# Interface1.net
KiCad netlist of a schematic drawn in Altium Designer
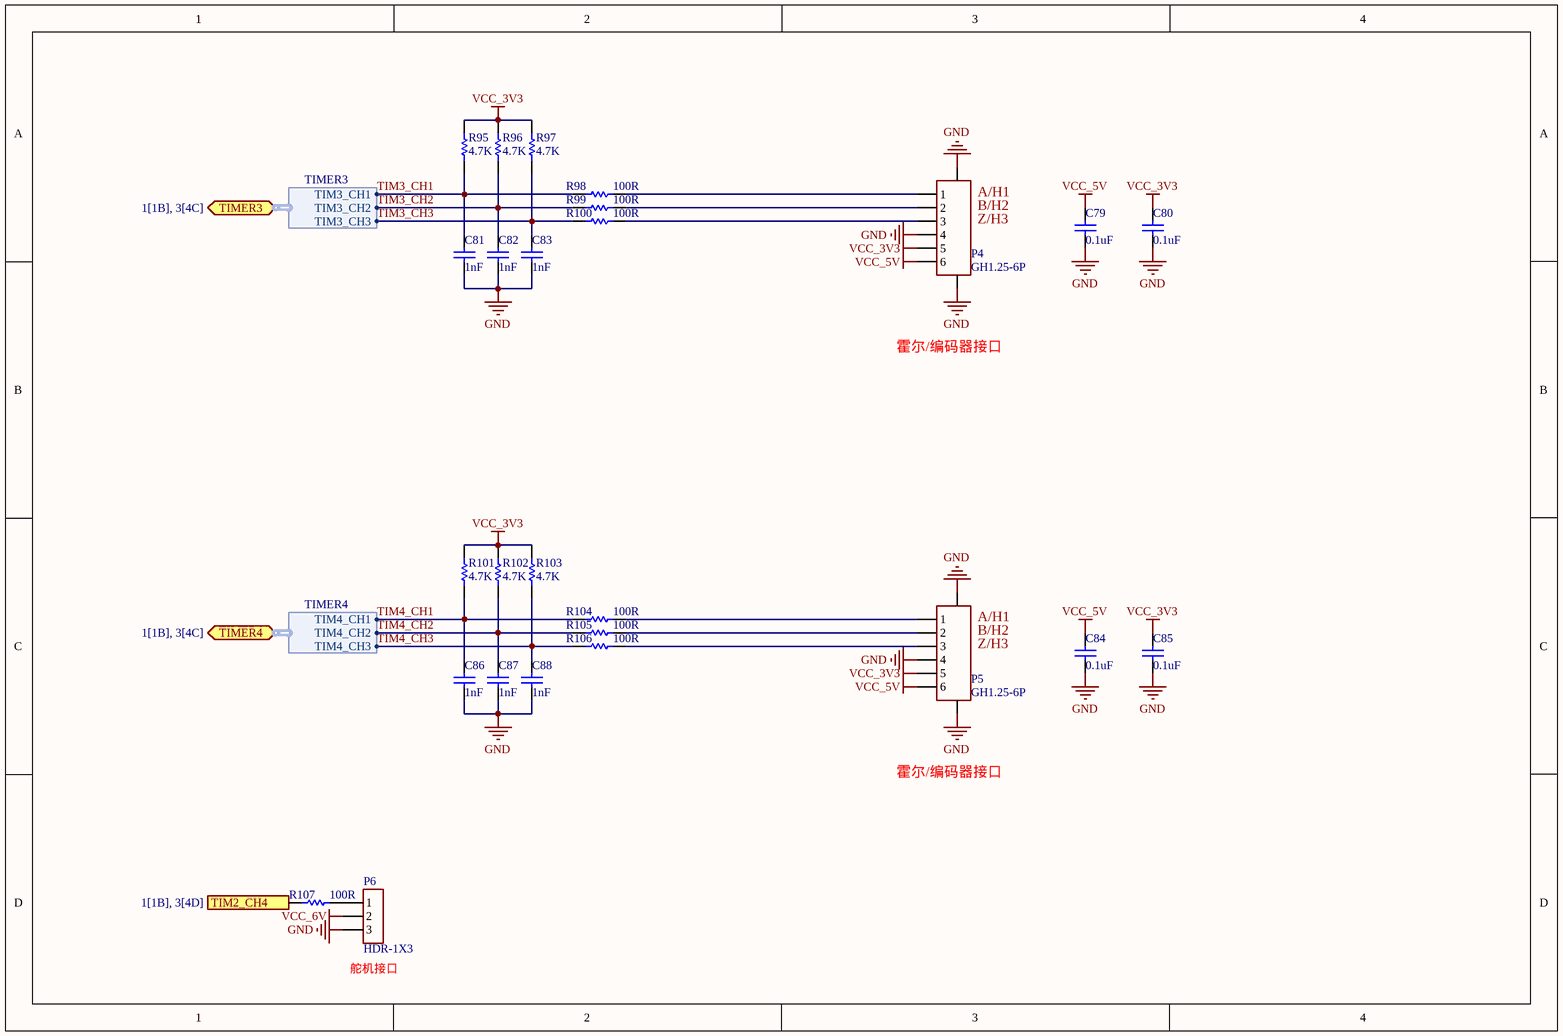
[diagram p0: Interface1.SchDoc]

(export (version "E")
  (design (tool "Eeschema 10.0.6"))
  (components
    (comp (ref "C79")
      (value "0.1uF")
      (footprint "C0603_NS")
      (description "Capacitor")
      (libsource (lib "Miscellaneous Devices") (part "Cap"))
    )
    (comp (ref "C80")
      (value "0.1uF")
      (footprint "C0603_NS")
      (description "Capacitor")
      (libsource (lib "Miscellaneous Devices") (part "Cap"))
    )
    (comp (ref "C81")
      (value "1nF")
      (footprint "C0603_NS")
      (description "Capacitor")
      (libsource (lib "Miscellaneous Devices") (part "Cap"))
    )
    (comp (ref "C82")
      (value "1nF")
      (footprint "C0603_NS")
      (description "Capacitor")
      (libsource (lib "Miscellaneous Devices") (part "Cap"))
    )
    (comp (ref "C83")
      (value "1nF")
      (footprint "C0603_NS")
      (description "Capacitor")
      (libsource (lib "Miscellaneous Devices") (part "Cap"))
    )
    (comp (ref "C84")
      (value "0.1uF")
      (footprint "C0603_NS")
      (description "Capacitor")
      (libsource (lib "Miscellaneous Devices") (part "Cap"))
    )
    (comp (ref "C85")
      (value "0.1uF")
      (footprint "C0603_NS")
      (description "Capacitor")
      (libsource (lib "Miscellaneous Devices") (part "Cap"))
    )
    (comp (ref "C86")
      (value "1nF")
      (footprint "C0603_NS")
      (description "Capacitor")
      (libsource (lib "Miscellaneous Devices") (part "Cap"))
    )
    (comp (ref "C87")
      (value "1nF")
      (footprint "C0603_NS")
      (description "Capacitor")
      (libsource (lib "Miscellaneous Devices") (part "Cap"))
    )
    (comp (ref "C88")
      (value "1nF")
      (footprint "C0603_NS")
      (description "Capacitor")
      (libsource (lib "Miscellaneous Devices") (part "Cap"))
    )
    (comp (ref "P4")
      (value "GH1.25-6P")
      (footprint "A1257WR-S-6P")
      (libsource (lib "my_library") (part "Header6"))
    )
    (comp (ref "P5")
      (value "GH1.25-6P")
      (footprint "A1257WR-S-6P")
      (libsource (lib "my_library") (part "Header6"))
    )
    (comp (ref "P6")
      (value "HDR-1X3")
      (footprint "HDR2.54-WI-3P")
      (libsource (lib "my_library") (part "HDR-1X3"))
    )
    (comp (ref "R95")
      (value "4.7K")
      (footprint "R0603_NS")
      (description "Resistor")
      (libsource (lib "Miscellaneous Devices") (part "Res1"))
    )
    (comp (ref "R96")
      (value "4.7K")
      (footprint "R0603_NS")
      (description "Resistor")
      (libsource (lib "Miscellaneous Devices") (part "Res1"))
    )
    (comp (ref "R97")
      (value "4.7K")
      (footprint "R0603_NS")
      (description "Resistor")
      (libsource (lib "Miscellaneous Devices") (part "Res1"))
    )
    (comp (ref "R98")
      (value "100R")
      (footprint "R0603_NS")
      (description "Resistor")
      (libsource (lib "Miscellaneous Devices") (part "Res1"))
    )
    (comp (ref "R99")
      (value "100R")
      (footprint "R0603_NS")
      (description "Resistor")
      (libsource (lib "Miscellaneous Devices") (part "Res1"))
    )
    (comp (ref "R100")
      (value "100R")
      (footprint "R0603_NS")
      (description "Resistor")
      (libsource (lib "Miscellaneous Devices") (part "Res1"))
    )
    (comp (ref "R101")
      (value "4.7K")
      (footprint "R0603_NS")
      (description "Resistor")
      (libsource (lib "Miscellaneous Devices") (part "Res1"))
    )
    (comp (ref "R102")
      (value "4.7K")
      (footprint "R0603_NS")
      (description "Resistor")
      (libsource (lib "Miscellaneous Devices") (part "Res1"))
    )
    (comp (ref "R103")
      (value "4.7K")
      (footprint "R0603_NS")
      (description "Resistor")
      (libsource (lib "Miscellaneous Devices") (part "Res1"))
    )
    (comp (ref "R104")
      (value "100R")
      (footprint "R0603_NS")
      (description "Resistor")
      (libsource (lib "Miscellaneous Devices") (part "Res1"))
    )
    (comp (ref "R105")
      (value "100R")
      (footprint "R0603_NS")
      (description "Resistor")
      (libsource (lib "Miscellaneous Devices") (part "Res1"))
    )
    (comp (ref "R106")
      (value "100R")
      (footprint "R0603_NS")
      (description "Resistor")
      (libsource (lib "Miscellaneous Devices") (part "Res1"))
    )
    (comp (ref "R107")
      (value "100R")
      (footprint "R0603_NS")
      (description "Resistor")
      (libsource (lib "Miscellaneous Devices") (part "Res1"))
    )
  )
  (nets
    (net (code "3") (name "/TIM2_CH4") (class "Default")
      (node (ref "R107") (pin "1") (pinfunction "1_1") (pintype "passive"))
    )
    (net (code "4") (name "/TIM3_CH1") (class "Default")
      (node (ref "C81") (pin "2") (pinfunction "2_2") (pintype "passive"))
      (node (ref "R95") (pin "1") (pinfunction "1_1") (pintype "passive"))
      (node (ref "R98") (pin "1") (pinfunction "1_1") (pintype "passive"))
    )
    (net (code "5") (name "/TIM3_CH2") (class "Default")
      (node (ref "C82") (pin "2") (pinfunction "2_2") (pintype "passive"))
      (node (ref "R96") (pin "1") (pinfunction "1_1") (pintype "passive"))
      (node (ref "R99") (pin "1") (pinfunction "1_1") (pintype "passive"))
    )
    (net (code "6") (name "/TIM3_CH3") (class "Default")
      (node (ref "C83") (pin "2") (pinfunction "2_2") (pintype "passive"))
      (node (ref "R100") (pin "1") (pinfunction "1_1") (pintype "passive"))
      (node (ref "R97") (pin "1") (pinfunction "1_1") (pintype "passive"))
    )
    (net (code "7") (name "/TIM4_CH1") (class "Default")
      (node (ref "C86") (pin "2") (pinfunction "2_2") (pintype "passive"))
      (node (ref "R101") (pin "1") (pinfunction "1_1") (pintype "passive"))
      (node (ref "R104") (pin "1") (pinfunction "1_1") (pintype "passive"))
    )
    (net (code "8") (name "/TIM4_CH2") (class "Default")
      (node (ref "C87") (pin "2") (pinfunction "2_2") (pintype "passive"))
      (node (ref "R102") (pin "1") (pinfunction "1_1") (pintype "passive"))
      (node (ref "R105") (pin "1") (pinfunction "1_1") (pintype "passive"))
    )
    (net (code "9") (name "/TIM4_CH3") (class "Default")
      (node (ref "C88") (pin "2") (pinfunction "2_2") (pintype "passive"))
      (node (ref "R103") (pin "1") (pinfunction "1_1") (pintype "passive"))
      (node (ref "R106") (pin "1") (pinfunction "1_1") (pintype "passive"))
    )
    (net (code "12") (name "GND") (class "Default")
      (node (ref "C79") (pin "1") (pinfunction "1_1") (pintype "passive"))
      (node (ref "C80") (pin "1") (pinfunction "1_1") (pintype "passive"))
      (node (ref "C81") (pin "1") (pinfunction "1_1") (pintype "passive"))
      (node (ref "C82") (pin "1") (pinfunction "1_1") (pintype "passive"))
      (node (ref "C83") (pin "1") (pinfunction "1_1") (pintype "passive"))
      (node (ref "C84") (pin "1") (pinfunction "1_1") (pintype "passive"))
      (node (ref "C85") (pin "1") (pinfunction "1_1") (pintype "passive"))
      (node (ref "C86") (pin "1") (pinfunction "1_1") (pintype "passive"))
      (node (ref "C87") (pin "1") (pinfunction "1_1") (pintype "passive"))
      (node (ref "C88") (pin "1") (pinfunction "1_1") (pintype "passive"))
      (node (ref "P4") (pin "0") (pinfunction "0_0") (pintype "passive"))
      (node (ref "P4") (pin "4") (pinfunction "4_4") (pintype "passive"))
      (node (ref "P5") (pin "0") (pinfunction "0_0") (pintype "passive"))
      (node (ref "P5") (pin "4") (pinfunction "4_4") (pintype "passive"))
      (node (ref "P6") (pin "3") (pinfunction "3_3") (pintype "passive"))
    )
    (net (code "13") (name "Net-(P4-Pad1)") (class "Default")
      (node (ref "P4") (pin "1") (pinfunction "1_1") (pintype "passive"))
      (node (ref "R98") (pin "2") (pinfunction "2_2") (pintype "passive"))
    )
    (net (code "14") (name "Net-(P4-Pad2)") (class "Default")
      (node (ref "P4") (pin "2") (pinfunction "2_2") (pintype "passive"))
      (node (ref "R99") (pin "2") (pinfunction "2_2") (pintype "passive"))
    )
    (net (code "15") (name "Net-(P4-Pad3)") (class "Default")
      (node (ref "P4") (pin "3") (pinfunction "3_3") (pintype "passive"))
      (node (ref "R100") (pin "2") (pinfunction "2_2") (pintype "passive"))
    )
    (net (code "16") (name "Net-(P5-Pad1)") (class "Default")
      (node (ref "P5") (pin "1") (pinfunction "1_1") (pintype "passive"))
      (node (ref "R104") (pin "2") (pinfunction "2_2") (pintype "passive"))
    )
    (net (code "17") (name "Net-(P5-Pad2)") (class "Default")
      (node (ref "P5") (pin "2") (pinfunction "2_2") (pintype "passive"))
      (node (ref "R105") (pin "2") (pinfunction "2_2") (pintype "passive"))
    )
    (net (code "18") (name "Net-(P5-Pad3)") (class "Default")
      (node (ref "P5") (pin "3") (pinfunction "3_3") (pintype "passive"))
      (node (ref "R106") (pin "2") (pinfunction "2_2") (pintype "passive"))
    )
    (net (code "19") (name "Net-(P6-Pad1)") (class "Default")
      (node (ref "P6") (pin "1") (pinfunction "1_1") (pintype "passive"))
      (node (ref "R107") (pin "2") (pinfunction "2_2") (pintype "passive"))
    )
    (net (code "20") (name "VCC_3V3") (class "Default")
      (node (ref "C80") (pin "2") (pinfunction "2_2") (pintype "passive"))
      (node (ref "C85") (pin "2") (pinfunction "2_2") (pintype "passive"))
      (node (ref "P4") (pin "5") (pinfunction "5_5") (pintype "passive"))
      (node (ref "P5") (pin "5") (pinfunction "5_5") (pintype "passive"))
      (node (ref "R101") (pin "2") (pinfunction "2_2") (pintype "passive"))
      (node (ref "R102") (pin "2") (pinfunction "2_2") (pintype "passive"))
      (node (ref "R103") (pin "2") (pinfunction "2_2") (pintype "passive"))
      (node (ref "R95") (pin "2") (pinfunction "2_2") (pintype "passive"))
      (node (ref "R96") (pin "2") (pinfunction "2_2") (pintype "passive"))
      (node (ref "R97") (pin "2") (pinfunction "2_2") (pintype "passive"))
    )
    (net (code "21") (name "VCC_5V") (class "Default")
      (node (ref "C79") (pin "2") (pinfunction "2_2") (pintype "passive"))
      (node (ref "C84") (pin "2") (pinfunction "2_2") (pintype "passive"))
      (node (ref "P4") (pin "6") (pinfunction "6_6") (pintype "passive"))
      (node (ref "P5") (pin "6") (pinfunction "6_6") (pintype "passive"))
    )
    (net (code "22") (name "VCC_6V") (class "Default")
      (node (ref "P6") (pin "2") (pinfunction "2_2") (pintype "passive"))
    )
  )
)
